# simplePDschematicsv1.net
KiCad netlist of a schematic drawn in EAGLE
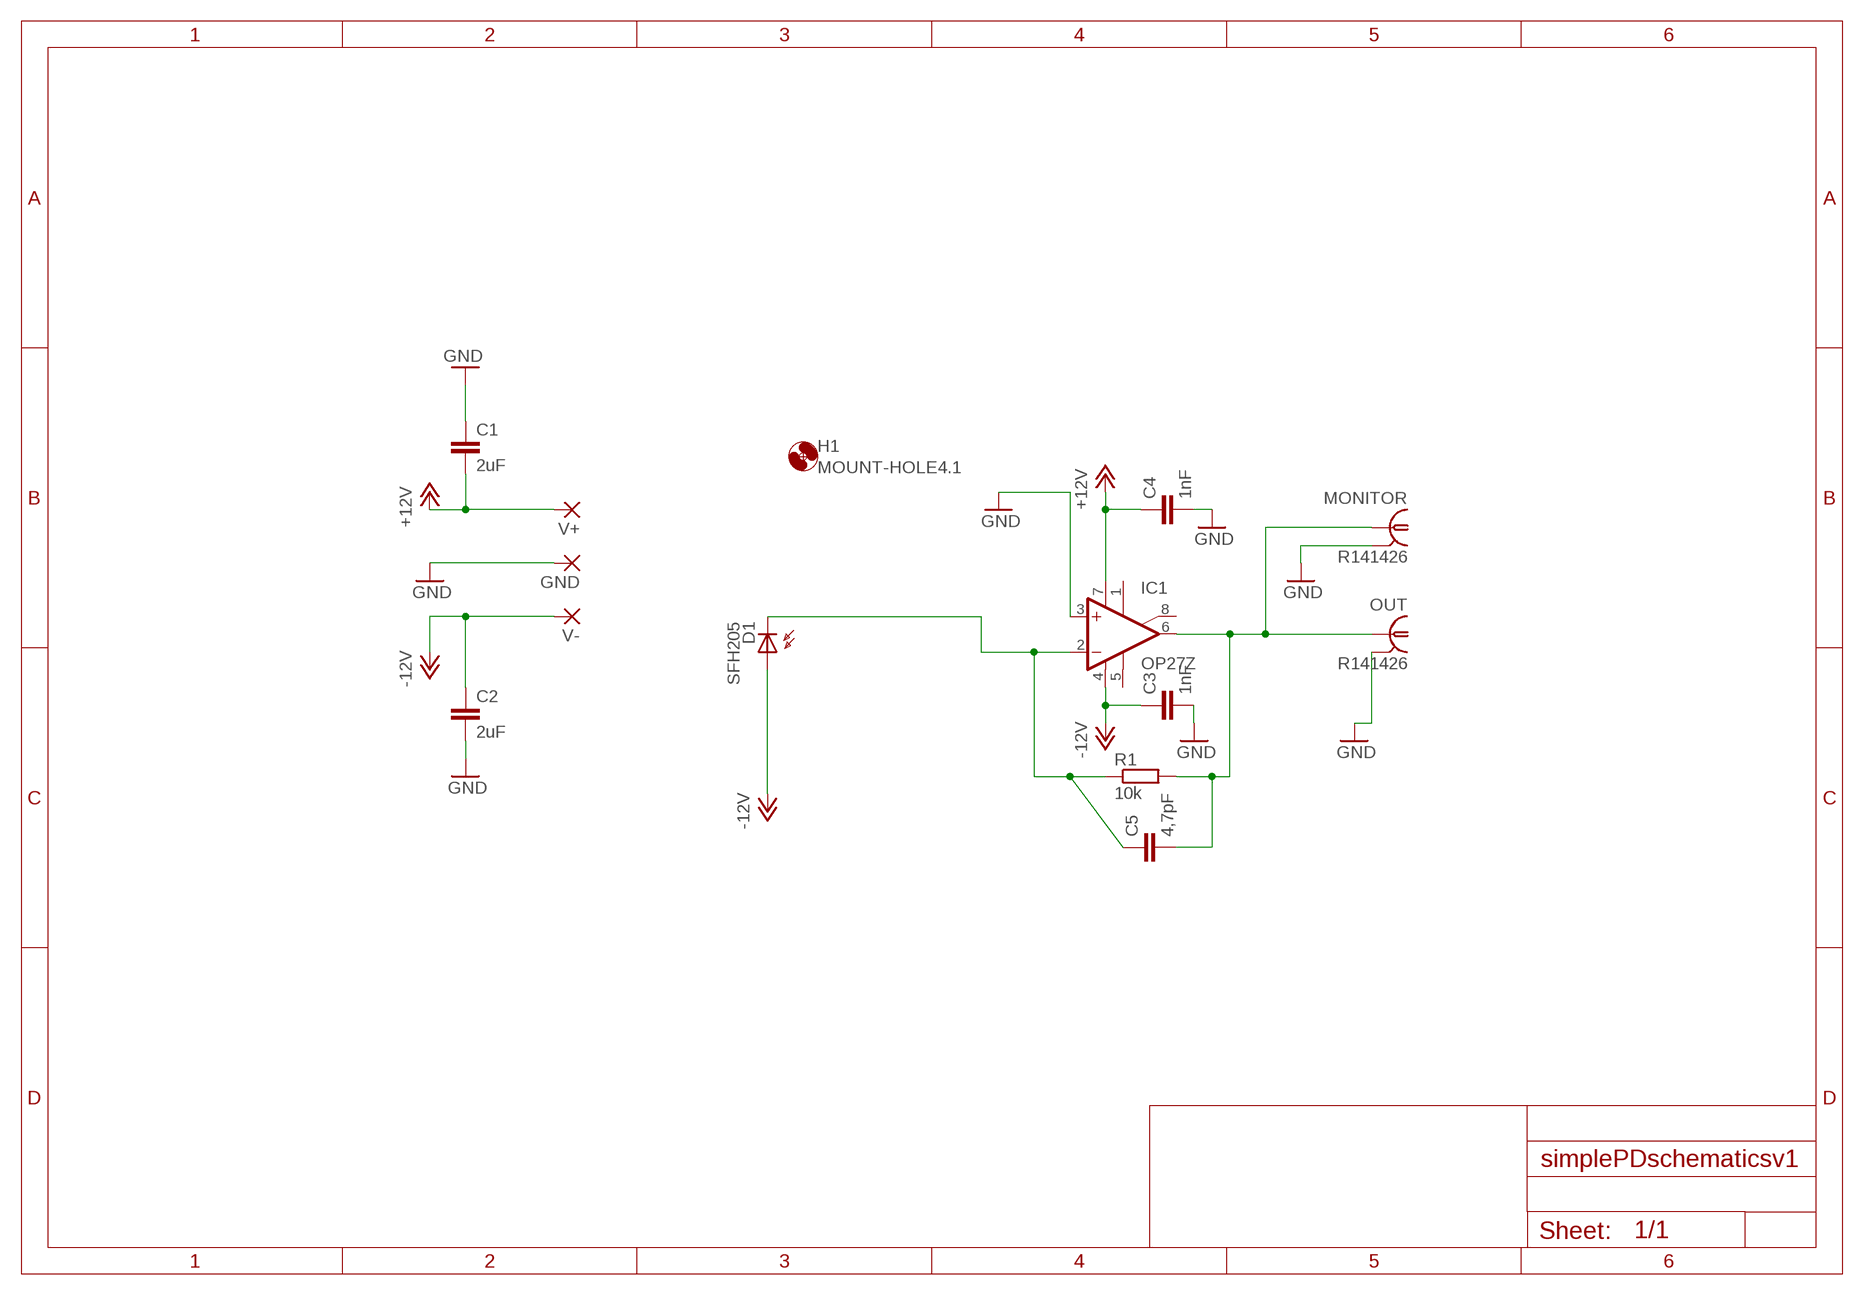
[diagram p0: schematic, sheet 1]

(export (version "E")
  (design (tool "Eeschema 10.0.6"))
  (components
    (comp (ref "C1")
      (value "2uF")
      (footprint "eagle-import:C050-075X075")
      (libsource (lib "eagle-import") (part "C-EU050-075X075"))
    )
    (comp (ref "C2")
      (value "2uF")
      (footprint "eagle-import:C050-075X075")
      (libsource (lib "eagle-import") (part "C-EU050-075X075"))
    )
    (comp (ref "C3")
      (value "1nF")
      (footprint "eagle-import:C025-050X050")
      (libsource (lib "eagle-import") (part "C-EU025-050X050"))
    )
    (comp (ref "C4")
      (value "1nF")
      (footprint "eagle-import:C025-050X050")
      (libsource (lib "eagle-import") (part "C-EU025-050X050"))
    )
    (comp (ref "C5")
      (value "4,7pF")
      (footprint "eagle-import:C025-050X050")
      (libsource (lib "eagle-import") (part "C-EU025-050X050"))
    )
    (comp (ref "D1")
      (value "SFH205")
      (footprint "eagle-import:SFH205")
      (libsource (lib "eagle-import") (part "SFH205"))
    )
    (comp (ref "GND")
      (value "1,6/0,9")
      (footprint "eagle-import:1,6_0,9")
      (libsource (lib "eagle-import") (part "1,6/0,9"))
    )
    (comp (ref "H1")
      (value "MOUNT-HOLE4.1")
      (footprint "eagle-import:4,1")
      (libsource (lib "eagle-import") (part "MOUNT-HOLE4.1"))
    )
    (comp (ref "IC1")
      (value "OP27Z")
      (footprint "eagle-import:DIL08")
      (libsource (lib "eagle-import") (part "OP27Z"))
    )
    (comp (ref "MONITOR")
      (value "R141426")
      (footprint "eagle-import:R141426")
      (fields (field (name "MF") "FARNELL") (field (name "MPN") "R141426161"))
      (libsource (lib "eagle-import") (part "R141426"))
    )
    (comp (ref "OUT")
      (value "R141426")
      (footprint "eagle-import:R141426")
      (fields (field (name "MF") "FARNELL") (field (name "MPN") "R141426161"))
      (libsource (lib "eagle-import") (part "R141426"))
    )
    (comp (ref "R1")
      (value "10k")
      (footprint "eagle-import:0207_10")
      (libsource (lib "eagle-import") (part "R-EU_0207/10"))
    )
    (comp (ref "V+")
      (value "1,6/0,9")
      (footprint "eagle-import:1,6_0,9")
      (libsource (lib "eagle-import") (part "1,6/0,9"))
    )
    (comp (ref "V-")
      (value "1,6/0,9")
      (footprint "eagle-import:1,6_0,9")
      (libsource (lib "eagle-import") (part "1,6/0,9"))
    )
  )
  (nets
    (net (code "1") (name "+12V") (class "Default")
      (node (ref "C1") (pin "2") (pinfunction "2_2") (pintype "passive"))
      (node (ref "C4") (pin "1") (pinfunction "1_1") (pintype "passive"))
      (node (ref "IC1") (pin "7") (pinfunction "V+_7") (pintype "power_in"))
      (node (ref "V+") (pin "1") (pinfunction "P_1") (pintype "passive"))
    )
    (net (code "2") (name "-12V") (class "Default")
      (node (ref "C2") (pin "1") (pinfunction "1_1") (pintype "passive"))
      (node (ref "C3") (pin "1") (pinfunction "1_1") (pintype "passive"))
      (node (ref "D1") (pin "A") (pinfunction "A_A") (pintype "passive"))
      (node (ref "IC1") (pin "4") (pinfunction "V-_4") (pintype "power_in"))
      (node (ref "V-") (pin "1") (pinfunction "P_1") (pintype "passive"))
    )
    (net (code "3") (name "GND") (class "Default")
      (node (ref "C1") (pin "1") (pinfunction "1_1") (pintype "passive"))
      (node (ref "C2") (pin "2") (pinfunction "2_2") (pintype "passive"))
      (node (ref "C3") (pin "2") (pinfunction "2_2") (pintype "passive"))
      (node (ref "C4") (pin "2") (pinfunction "2_2") (pintype "passive"))
      (node (ref "GND") (pin "1") (pinfunction "P_1") (pintype "passive"))
      (node (ref "IC1") (pin "3") (pinfunction "+IN_3") (pintype "input"))
      (node (ref "MONITOR") (pin "2") (pinfunction "2_2") (pintype "passive"))
      (node (ref "MONITOR") (pin "3") (pinfunction "2_3") (pintype "passive"))
      (node (ref "MONITOR") (pin "4") (pinfunction "2_4") (pintype "passive"))
      (node (ref "MONITOR") (pin "5") (pinfunction "2_5") (pintype "passive"))
      (node (ref "OUT") (pin "2") (pinfunction "2_2") (pintype "passive"))
      (node (ref "OUT") (pin "3") (pinfunction "2_3") (pintype "passive"))
      (node (ref "OUT") (pin "4") (pinfunction "2_4") (pintype "passive"))
      (node (ref "OUT") (pin "5") (pinfunction "2_5") (pintype "passive"))
    )
    (net (code "4") (name "Net-(D1-C)") (class "Default")
      (node (ref "C5") (pin "1") (pinfunction "1_1") (pintype "passive"))
      (node (ref "D1") (pin "K") (pinfunction "C_K") (pintype "passive"))
      (node (ref "IC1") (pin "2") (pinfunction "-IN_2") (pintype "input"))
      (node (ref "R1") (pin "1") (pinfunction "1_1") (pintype "passive"))
    )
    (net (code "5") (name "Net-(IC1-OUT)") (class "Default")
      (node (ref "C5") (pin "2") (pinfunction "2_2") (pintype "passive"))
      (node (ref "IC1") (pin "6") (pinfunction "OUT_6") (pintype "output"))
      (node (ref "MONITOR") (pin "1") (pinfunction "1_1") (pintype "passive"))
      (node (ref "OUT") (pin "1") (pinfunction "1_1") (pintype "passive"))
      (node (ref "R1") (pin "2") (pinfunction "2_2") (pintype "passive"))
    )
    (net (code "6") (name "unconnected-(IC1-ON1-Pad1)") (class "Default")
      (node (ref "IC1") (pin "1") (pinfunction "ON1_1") (pintype "passive"))
    )
    (net (code "7") (name "unconnected-(IC1-ON2-Pad8)") (class "Default")
      (node (ref "IC1") (pin "8") (pinfunction "ON2_8") (pintype "passive"))
    )
    (net (code "8") (name "unconnected-(IC1-OPT-Pad5)") (class "Default")
      (node (ref "IC1") (pin "5") (pinfunction "OPT_5") (pintype "passive"))
    )
  )
)
